# Microphone-Arm_V1_0.net
KiCad netlist of a schematic drawn in Altium Designer
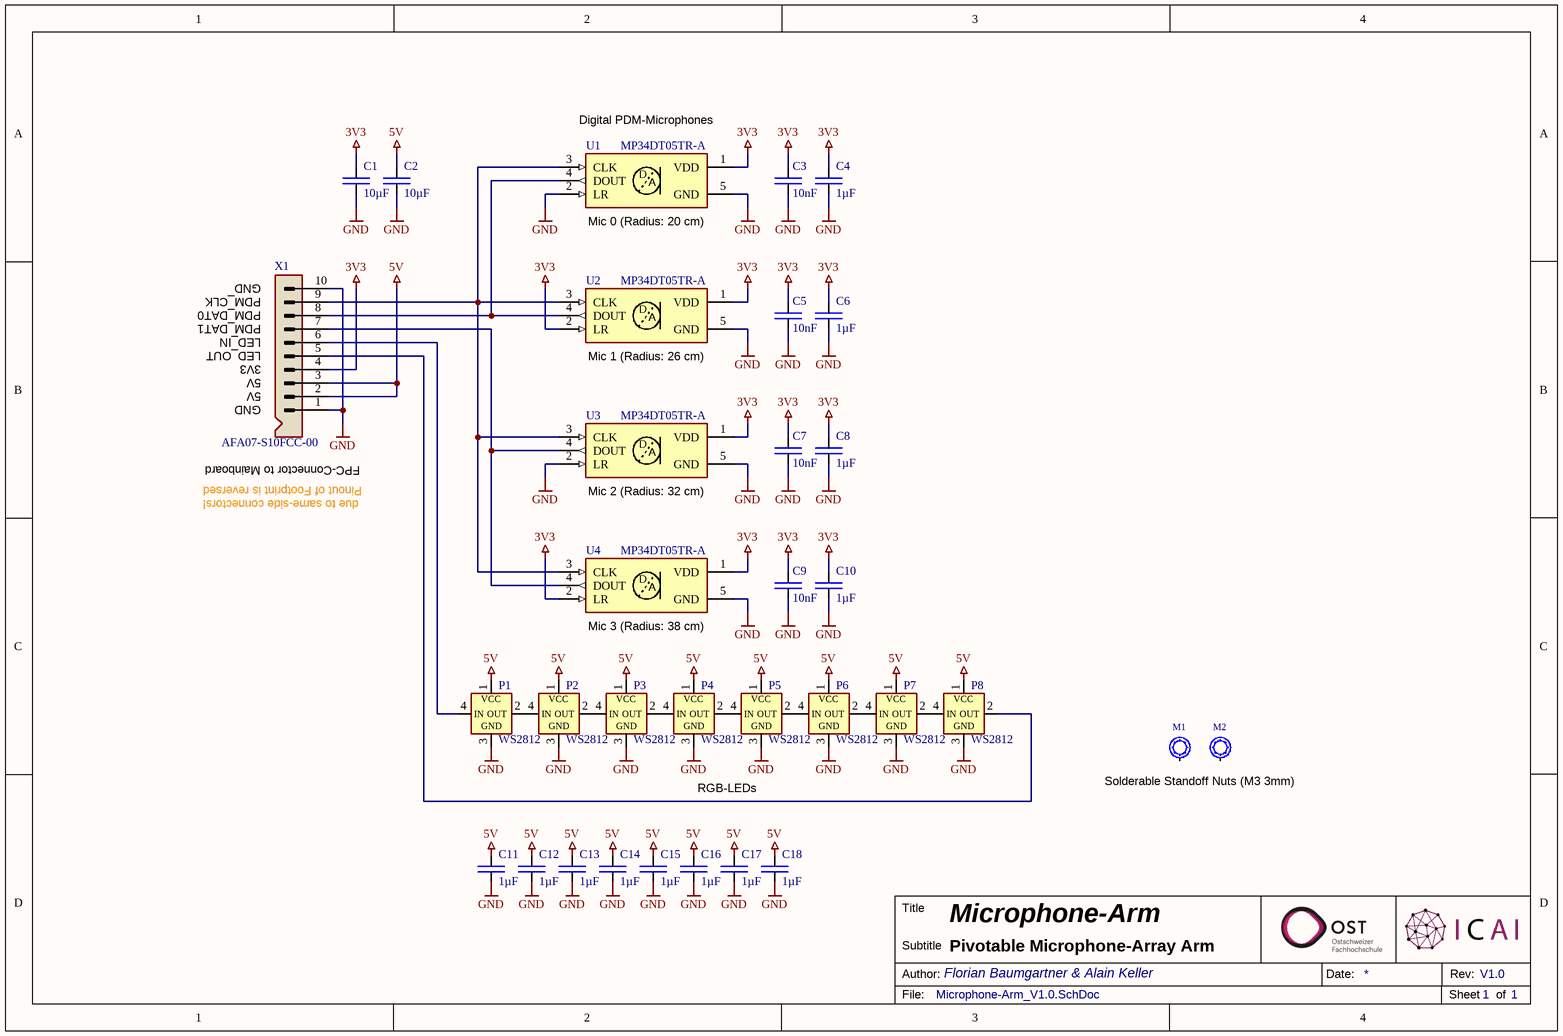
[diagram p0: Microphone-Arm_V1.0.SchDoc]

(export (version "E")
  (design (tool "Eeschema 10.0.6"))
  (components
    (comp (ref "C1")
      (value "10µF")
      (footprint "SMD Keramikkondensator 1206")
      (description "SMD Ceramic Capacitor E6")
      (libsource (lib "Ceramic Capacitors-E6") (part "E6 - 10uF"))
    )
    (comp (ref "C2")
      (value "10µF")
      (footprint "SMD Keramikkondensator 1206")
      (description "SMD Ceramic Capacitor E6")
      (libsource (lib "Ceramic Capacitors-E6") (part "E6 - 10uF"))
    )
    (comp (ref "C3")
      (value "10nF")
      (footprint "SMD Keramikkondensator 0603")
      (description "CAP-MK")
      (libsource (lib "AudioAmp") (part "C-CAPACITOR"))
    )
    (comp (ref "C4")
      (value "1µF")
      (footprint "SMD Keramikkondensator 0603")
      (description "CAP-MK")
      (libsource (lib "AudioAmp") (part "C-CAPACITOR"))
    )
    (comp (ref "C5")
      (value "10nF")
      (footprint "SMD Keramikkondensator 0603")
      (description "CAP-MK")
      (libsource (lib "AudioAmp") (part "C-CAPACITOR"))
    )
    (comp (ref "C6")
      (value "1µF")
      (footprint "SMD Keramikkondensator 0603")
      (description "CAP-MK")
      (libsource (lib "AudioAmp") (part "C-CAPACITOR"))
    )
    (comp (ref "C7")
      (value "10nF")
      (footprint "SMD Keramikkondensator 0603")
      (description "CAP-MK")
      (libsource (lib "AudioAmp") (part "C-CAPACITOR"))
    )
    (comp (ref "C8")
      (value "1µF")
      (footprint "SMD Keramikkondensator 0603")
      (description "CAP-MK")
      (libsource (lib "AudioAmp") (part "C-CAPACITOR"))
    )
    (comp (ref "C9")
      (value "10nF")
      (footprint "SMD Keramikkondensator 0603")
      (description "CAP-MK")
      (libsource (lib "AudioAmp") (part "C-CAPACITOR"))
    )
    (comp (ref "C10")
      (value "1µF")
      (footprint "SMD Keramikkondensator 0603")
      (description "CAP-MK")
      (libsource (lib "AudioAmp") (part "C-CAPACITOR"))
    )
    (comp (ref "C11")
      (value "1µF")
      (footprint "SMD Keramikkondensator 0603")
      (description "CAP-MK")
      (libsource (lib "AudioAmp") (part "C-CAPACITOR"))
    )
    (comp (ref "C12")
      (value "1µF")
      (footprint "SMD Keramikkondensator 0603")
      (description "CAP-MK")
      (libsource (lib "AudioAmp") (part "C-CAPACITOR"))
    )
    (comp (ref "C13")
      (value "1µF")
      (footprint "SMD Keramikkondensator 0603")
      (description "CAP-MK")
      (libsource (lib "AudioAmp") (part "C-CAPACITOR"))
    )
    (comp (ref "C14")
      (value "1µF")
      (footprint "SMD Keramikkondensator 0603")
      (description "CAP-MK")
      (libsource (lib "AudioAmp") (part "C-CAPACITOR"))
    )
    (comp (ref "C15")
      (value "1µF")
      (footprint "SMD Keramikkondensator 0603")
      (description "CAP-MK")
      (libsource (lib "AudioAmp") (part "C-CAPACITOR"))
    )
    (comp (ref "C16")
      (value "1µF")
      (footprint "SMD Keramikkondensator 0603")
      (description "CAP-MK")
      (libsource (lib "AudioAmp") (part "C-CAPACITOR"))
    )
    (comp (ref "C17")
      (value "1µF")
      (footprint "SMD Keramikkondensator 0603")
      (description "CAP-MK")
      (libsource (lib "AudioAmp") (part "C-CAPACITOR"))
    )
    (comp (ref "C18")
      (value "1µF")
      (footprint "SMD Keramikkondensator 0603")
      (description "CAP-MK")
      (libsource (lib "AudioAmp") (part "C-CAPACITOR"))
    )
    (comp (ref "M1")
      (value "SMTSO-M3-3ET")
      (footprint "SMD Solder-Nut (M3 3mm)")
      (description "Solderable Standoff Nut")
      (libsource (lib "Velotour_2022") (part "M-Spacer_M3_3mm"))
    )
    (comp (ref "M2")
      (value "SMTSO-M3-3ET")
      (footprint "SMD Solder-Nut (M3 3mm)")
      (description "Solderable Standoff Nut")
      (libsource (lib "Velotour_2022") (part "M-Spacer_M3_3mm"))
    )
    (comp (ref "P1")
      (value "WS2812")
      (footprint "SMD LED WS2812B-0807")
      (description "Smart RGB-LED")
      (libsource (lib "Acquisition-System") (part "P-WS2812B-0807"))
    )
    (comp (ref "P2")
      (value "WS2812")
      (footprint "SMD LED WS2812B-0807")
      (description "Smart RGB-LED")
      (libsource (lib "Acquisition-System") (part "P-WS2812B-0807"))
    )
    (comp (ref "P3")
      (value "WS2812")
      (footprint "SMD LED WS2812B-0807")
      (description "Smart RGB-LED")
      (libsource (lib "Acquisition-System") (part "P-WS2812B-0807"))
    )
    (comp (ref "P4")
      (value "WS2812")
      (footprint "SMD LED WS2812B-0807")
      (description "Smart RGB-LED")
      (libsource (lib "Acquisition-System") (part "P-WS2812B-0807"))
    )
    (comp (ref "P5")
      (value "WS2812")
      (footprint "SMD LED WS2812B-0807")
      (description "Smart RGB-LED")
      (libsource (lib "Acquisition-System") (part "P-WS2812B-0807"))
    )
    (comp (ref "P6")
      (value "WS2812")
      (footprint "SMD LED WS2812B-0807")
      (description "Smart RGB-LED")
      (libsource (lib "Acquisition-System") (part "P-WS2812B-0807"))
    )
    (comp (ref "P7")
      (value "WS2812")
      (footprint "SMD LED WS2812B-0807")
      (description "Smart RGB-LED")
      (libsource (lib "Acquisition-System") (part "P-WS2812B-0807"))
    )
    (comp (ref "P8")
      (value "WS2812")
      (footprint "SMD LED WS2812B-0807")
      (description "Smart RGB-LED")
      (libsource (lib "Acquisition-System") (part "P-WS2812B-0807"))
    )
    (comp (ref "U1")
      (value "MP34DT05TR-A")
      (footprint "SMD Microphone (MP34DT05TR-A)")
      (description "Digital PDM MEMS Microphone (Top Port)")
      (libsource (lib "Microphone-Boards") (part "U-MP34DT05TR-A"))
    )
    (comp (ref "U2")
      (value "MP34DT05TR-A")
      (footprint "SMD Microphone (MP34DT05TR-A)")
      (description "Digital PDM MEMS Microphone (Top Port)")
      (libsource (lib "Microphone-Boards") (part "U-MP34DT05TR-A"))
    )
    (comp (ref "U3")
      (value "MP34DT05TR-A")
      (footprint "SMD Microphone (MP34DT05TR-A)")
      (description "Digital PDM MEMS Microphone (Top Port)")
      (libsource (lib "Microphone-Boards") (part "U-MP34DT05TR-A"))
    )
    (comp (ref "U4")
      (value "MP34DT05TR-A")
      (footprint "SMD Microphone (MP34DT05TR-A)")
      (description "Digital PDM MEMS Microphone (Top Port)")
      (libsource (lib "Microphone-Boards") (part "U-MP34DT05TR-A"))
    )
    (comp (ref "X1")
      (value "AFA07-S10FCC-00")
      (footprint "SMD Connector (AFA07-S10FCC-00) [Reversed]")
      (description "FPC-Connector (10-Pin, Slide-Lock,  Bottom Contact)")
      (libsource (lib "Mainboard") (part "X-FPC-Connector (10-Pin)"))
    )
  )
  (nets
    (net (code "1") (name "3V3") (class "Default")
      (node (ref "C1") (pin "2") (pinfunction "2_2") (pintype "passive"))
      (node (ref "C10") (pin "2") (pinfunction "2_2") (pintype "passive"))
      (node (ref "C3") (pin "2") (pinfunction "2_2") (pintype "passive"))
      (node (ref "C4") (pin "2") (pinfunction "2_2") (pintype "passive"))
      (node (ref "C5") (pin "2") (pinfunction "2_2") (pintype "passive"))
      (node (ref "C6") (pin "2") (pinfunction "2_2") (pintype "passive"))
      (node (ref "C7") (pin "2") (pinfunction "2_2") (pintype "passive"))
      (node (ref "C8") (pin "2") (pinfunction "2_2") (pintype "passive"))
      (node (ref "C9") (pin "2") (pinfunction "2_2") (pintype "passive"))
      (node (ref "U1") (pin "1") (pinfunction "VDD_1") (pintype "power_in"))
      (node (ref "U2") (pin "1") (pinfunction "VDD_1") (pintype "power_in"))
      (node (ref "U2") (pin "2") (pinfunction "LR_2") (pintype "input"))
      (node (ref "U3") (pin "1") (pinfunction "VDD_1") (pintype "power_in"))
      (node (ref "U4") (pin "1") (pinfunction "VDD_1") (pintype "power_in"))
      (node (ref "U4") (pin "2") (pinfunction "LR_2") (pintype "input"))
      (node (ref "X1") (pin "4") (pinfunction "4_4") (pintype "passive"))
    )
    (net (code "2") (name "5V") (class "Default")
      (node (ref "C11") (pin "2") (pinfunction "2_2") (pintype "passive"))
      (node (ref "C12") (pin "2") (pinfunction "2_2") (pintype "passive"))
      (node (ref "C13") (pin "2") (pinfunction "2_2") (pintype "passive"))
      (node (ref "C14") (pin "2") (pinfunction "2_2") (pintype "passive"))
      (node (ref "C15") (pin "2") (pinfunction "2_2") (pintype "passive"))
      (node (ref "C16") (pin "2") (pinfunction "2_2") (pintype "passive"))
      (node (ref "C17") (pin "2") (pinfunction "2_2") (pintype "passive"))
      (node (ref "C18") (pin "2") (pinfunction "2_2") (pintype "passive"))
      (node (ref "C2") (pin "2") (pinfunction "2_2") (pintype "passive"))
      (node (ref "P1") (pin "1") (pinfunction "VCC_1") (pintype "power_in"))
      (node (ref "P2") (pin "1") (pinfunction "VCC_1") (pintype "power_in"))
      (node (ref "P3") (pin "1") (pinfunction "VCC_1") (pintype "power_in"))
      (node (ref "P4") (pin "1") (pinfunction "VCC_1") (pintype "power_in"))
      (node (ref "P5") (pin "1") (pinfunction "VCC_1") (pintype "power_in"))
      (node (ref "P6") (pin "1") (pinfunction "VCC_1") (pintype "power_in"))
      (node (ref "P7") (pin "1") (pinfunction "VCC_1") (pintype "power_in"))
      (node (ref "P8") (pin "1") (pinfunction "VCC_1") (pintype "power_in"))
      (node (ref "X1") (pin "2") (pinfunction "2_2") (pintype "passive"))
      (node (ref "X1") (pin "3") (pinfunction "3_3") (pintype "passive"))
    )
    (net (code "3") (name "GND") (class "Default")
      (node (ref "C1") (pin "1") (pinfunction "1_1") (pintype "passive"))
      (node (ref "C10") (pin "1") (pinfunction "1_1") (pintype "passive"))
      (node (ref "C11") (pin "1") (pinfunction "1_1") (pintype "passive"))
      (node (ref "C12") (pin "1") (pinfunction "1_1") (pintype "passive"))
      (node (ref "C13") (pin "1") (pinfunction "1_1") (pintype "passive"))
      (node (ref "C14") (pin "1") (pinfunction "1_1") (pintype "passive"))
      (node (ref "C15") (pin "1") (pinfunction "1_1") (pintype "passive"))
      (node (ref "C16") (pin "1") (pinfunction "1_1") (pintype "passive"))
      (node (ref "C17") (pin "1") (pinfunction "1_1") (pintype "passive"))
      (node (ref "C18") (pin "1") (pinfunction "1_1") (pintype "passive"))
      (node (ref "C2") (pin "1") (pinfunction "1_1") (pintype "passive"))
      (node (ref "C3") (pin "1") (pinfunction "1_1") (pintype "passive"))
      (node (ref "C4") (pin "1") (pinfunction "1_1") (pintype "passive"))
      (node (ref "C5") (pin "1") (pinfunction "1_1") (pintype "passive"))
      (node (ref "C6") (pin "1") (pinfunction "1_1") (pintype "passive"))
      (node (ref "C7") (pin "1") (pinfunction "1_1") (pintype "passive"))
      (node (ref "C8") (pin "1") (pinfunction "1_1") (pintype "passive"))
      (node (ref "C9") (pin "1") (pinfunction "1_1") (pintype "passive"))
      (node (ref "P1") (pin "3") (pinfunction "GND_3") (pintype "power_in"))
      (node (ref "P2") (pin "3") (pinfunction "GND_3") (pintype "power_in"))
      (node (ref "P3") (pin "3") (pinfunction "GND_3") (pintype "power_in"))
      (node (ref "P4") (pin "3") (pinfunction "GND_3") (pintype "power_in"))
      (node (ref "P5") (pin "3") (pinfunction "GND_3") (pintype "power_in"))
      (node (ref "P6") (pin "3") (pinfunction "GND_3") (pintype "power_in"))
      (node (ref "P7") (pin "3") (pinfunction "GND_3") (pintype "power_in"))
      (node (ref "P8") (pin "3") (pinfunction "GND_3") (pintype "power_in"))
      (node (ref "U1") (pin "2") (pinfunction "LR_2") (pintype "input"))
      (node (ref "U1") (pin "5") (pinfunction "GND_5") (pintype "power_in"))
      (node (ref "U2") (pin "5") (pinfunction "GND_5") (pintype "power_in"))
      (node (ref "U3") (pin "2") (pinfunction "LR_2") (pintype "input"))
      (node (ref "U3") (pin "5") (pinfunction "GND_5") (pintype "power_in"))
      (node (ref "U4") (pin "5") (pinfunction "GND_5") (pintype "power_in"))
      (node (ref "X1") (pin "1") (pinfunction "1_1") (pintype "passive"))
      (node (ref "X1") (pin "10") (pinfunction "10_10") (pintype "passive"))
    )
    (net (code "4") (name "Net-(P1-IN)") (class "Default")
      (node (ref "P1") (pin "4") (pinfunction "IN_4") (pintype "passive"))
      (node (ref "X1") (pin "6") (pinfunction "6_6") (pintype "passive"))
    )
    (net (code "5") (name "Net-(P1-OUT)") (class "Default")
      (node (ref "P1") (pin "2") (pinfunction "OUT_2") (pintype "passive"))
      (node (ref "P2") (pin "4") (pinfunction "IN_4") (pintype "passive"))
    )
    (net (code "6") (name "Net-(P2-OUT)") (class "Default")
      (node (ref "P2") (pin "2") (pinfunction "OUT_2") (pintype "passive"))
      (node (ref "P3") (pin "4") (pinfunction "IN_4") (pintype "passive"))
    )
    (net (code "7") (name "Net-(P3-OUT)") (class "Default")
      (node (ref "P3") (pin "2") (pinfunction "OUT_2") (pintype "passive"))
      (node (ref "P4") (pin "4") (pinfunction "IN_4") (pintype "passive"))
    )
    (net (code "8") (name "Net-(P4-OUT)") (class "Default")
      (node (ref "P4") (pin "2") (pinfunction "OUT_2") (pintype "passive"))
      (node (ref "P5") (pin "4") (pinfunction "IN_4") (pintype "passive"))
    )
    (net (code "9") (name "Net-(P5-OUT)") (class "Default")
      (node (ref "P5") (pin "2") (pinfunction "OUT_2") (pintype "passive"))
      (node (ref "P6") (pin "4") (pinfunction "IN_4") (pintype "passive"))
    )
    (net (code "10") (name "Net-(P6-OUT)") (class "Default")
      (node (ref "P6") (pin "2") (pinfunction "OUT_2") (pintype "passive"))
      (node (ref "P7") (pin "4") (pinfunction "IN_4") (pintype "passive"))
    )
    (net (code "11") (name "Net-(P7-OUT)") (class "Default")
      (node (ref "P7") (pin "2") (pinfunction "OUT_2") (pintype "passive"))
      (node (ref "P8") (pin "4") (pinfunction "IN_4") (pintype "passive"))
    )
    (net (code "12") (name "Net-(P8-OUT)") (class "Default")
      (node (ref "P8") (pin "2") (pinfunction "OUT_2") (pintype "passive"))
      (node (ref "X1") (pin "5") (pinfunction "5_5") (pintype "passive"))
    )
    (net (code "13") (name "Net-(U1-CLK)") (class "Default")
      (node (ref "U1") (pin "3") (pinfunction "CLK_3") (pintype "input"))
      (node (ref "U2") (pin "3") (pinfunction "CLK_3") (pintype "input"))
      (node (ref "U3") (pin "3") (pinfunction "CLK_3") (pintype "input"))
      (node (ref "U4") (pin "3") (pinfunction "CLK_3") (pintype "input"))
      (node (ref "X1") (pin "9") (pinfunction "9_9") (pintype "passive"))
    )
    (net (code "14") (name "Net-(U1-DOUT)") (class "Default")
      (node (ref "U1") (pin "4") (pinfunction "DOUT_4") (pintype "output"))
      (node (ref "U2") (pin "4") (pinfunction "DOUT_4") (pintype "output"))
      (node (ref "X1") (pin "8") (pinfunction "8_8") (pintype "passive"))
    )
    (net (code "15") (name "Net-(U3-DOUT)") (class "Default")
      (node (ref "U3") (pin "4") (pinfunction "DOUT_4") (pintype "output"))
      (node (ref "U4") (pin "4") (pinfunction "DOUT_4") (pintype "output"))
      (node (ref "X1") (pin "7") (pinfunction "7_7") (pintype "passive"))
    )
    (net (code "16") (name "unconnected-(M1-Pad1)") (class "Default")
      (node (ref "M1") (pin "1") (pinfunction "1_1") (pintype "passive"))
    )
    (net (code "17") (name "unconnected-(M2-Pad1)") (class "Default")
      (node (ref "M2") (pin "1") (pinfunction "1_1") (pintype "passive"))
    )
  )
)
